# PX4FMUv2_4_6_1.net
KiCad netlist of a schematic drawn in Altium Designer
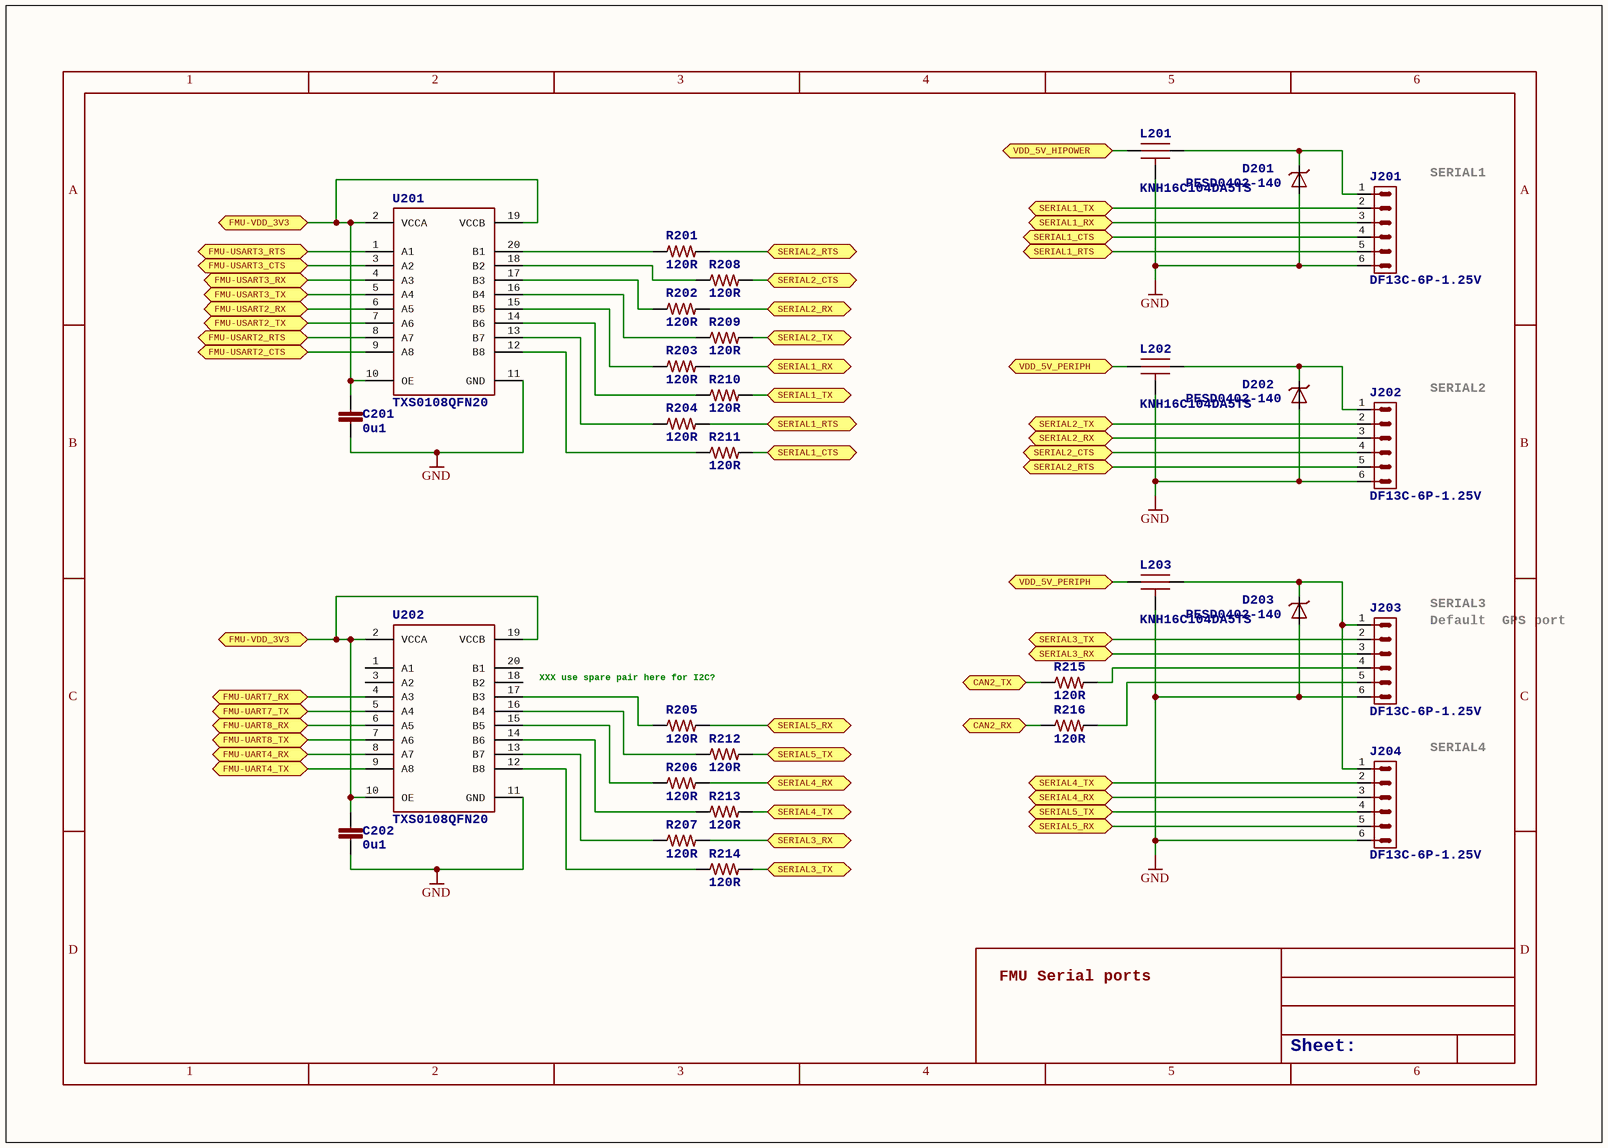
[diagram p0: PX4FMUv2.4.6_1.SchDoc]

(export (version "E")
  (design (tool "Eeschema 10.0.6"))
  (components
    (comp (ref "C201")
      (value "0u1")
      (footprint "0402-CAP")
      (description "CapacitorStandard 0603 ceramic capacitor, and 0.1\" leaded capacitor.")
      (fields (field (name "PARTNO") "CC0402ZRY5V7BB104"))
      (libsource (lib "pixhawk2") (part "CAP0402"))
    )
    (comp (ref "C202")
      (value "0u1")
      (footprint "0402-CAP")
      (description "CapacitorStandard 0603 ceramic capacitor, and 0.1\" leaded capacitor.")
      (fields (field (name "PARTNO") "CC0402ZRY5V7BB104"))
      (libsource (lib "pixhawk2") (part "CAP0402"))
    )
    (comp (ref "D201")
      (value "PESD0402-140")
      (footprint "0402-TVS")
      (libsource (lib "pixhawk2") (part "DIODE-TVS"))
    )
    (comp (ref "D202")
      (value "PESD0402-140")
      (footprint "0402-TVS")
      (libsource (lib "pixhawk2") (part "DIODE-TVS"))
    )
    (comp (ref "D203")
      (value "PESD0402-140")
      (footprint "0402-TVS")
      (libsource (lib "pixhawk2") (part "DIODE-TVS"))
    )
    (comp (ref "J201")
      (value "DF13C-6P-1.25V")
      (footprint "DF13C-6P-1.25V")
      (description "DF13-6P 1.25mm Pitch Miniature Crimping Connector.")
      (fields (field (name "PARTNO") "DF13C-6P-1.25V(20)"))
      (libsource (lib "con-hirose-df13") (part "DF13-6P-1.25V"))
    )
    (comp (ref "J202")
      (value "DF13C-6P-1.25V")
      (footprint "DF13C-6P-1.25V")
      (description "DF13-6P 1.25mm Pitch Miniature Crimping Connector.")
      (fields (field (name "PARTNO") "DF13C-6P-1.25V(20)"))
      (libsource (lib "con-hirose-df13") (part "DF13-6P-1.25V"))
    )
    (comp (ref "J203")
      (value "DF13C-6P-1.25V")
      (footprint "DF13C-6P-1.25V")
      (description "DF13-6P 1.25mm Pitch Miniature Crimping Connector.")
      (fields (field (name "PARTNO") "DF13C-6P-1.25V(20)"))
      (libsource (lib "con-hirose-df13") (part "DF13-6P-1.25V"))
    )
    (comp (ref "J204")
      (value "DF13C-6P-1.25V")
      (footprint "DF13C-6P-1.25V")
      (description "DF13-6P 1.25mm Pitch Miniature Crimping Connector.")
      (fields (field (name "PARTNO") "DF13C-6P-1.25V(20)"))
      (libsource (lib "con-hirose-df13") (part "DF13-6P-1.25V"))
    )
    (comp (ref "L201")
      (value "KNH16C104DA5TS")
      (footprint "KYOCERA-KNH16-DA")
      (description "Kyocera KNH16C104DA5TS EMI filter")
      (libsource (lib "pixhawk2") (part "KNH16C104DA5TS"))
    )
    (comp (ref "L202")
      (value "KNH16C104DA5TS")
      (footprint "KYOCERA-KNH16-DA")
      (description "Kyocera KNH16C104DA5TS EMI filter")
      (libsource (lib "pixhawk2") (part "KNH16C104DA5TS"))
    )
    (comp (ref "L203")
      (value "KNH16C104DA5TS")
      (footprint "KYOCERA-KNH16-DA")
      (description "Kyocera KNH16C104DA5TS EMI filter")
      (libsource (lib "pixhawk2") (part "KNH16C104DA5TS"))
    )
    (comp (ref "R201")
      (value "120R")
      (footprint "0402-RES")
      (fields (field (name "PARTNO") "RC0402FR-07120RL"))
      (libsource (lib "pixhawk2") (part "RESISTOR0402-RES"))
    )
    (comp (ref "R202")
      (value "120R")
      (footprint "0402-RES")
      (fields (field (name "PARTNO") "RC0402FR-07120RL"))
      (libsource (lib "pixhawk2") (part "RESISTOR0402-RES"))
    )
    (comp (ref "R203")
      (value "120R")
      (footprint "0402-RES")
      (fields (field (name "PARTNO") "RC0402FR-07120RL"))
      (libsource (lib "pixhawk2") (part "RESISTOR0402-RES"))
    )
    (comp (ref "R204")
      (value "120R")
      (footprint "0402-RES")
      (fields (field (name "PARTNO") "RC0402FR-07120RL"))
      (libsource (lib "pixhawk2") (part "RESISTOR0402-RES"))
    )
    (comp (ref "R205")
      (value "120R")
      (footprint "0402-RES")
      (fields (field (name "PARTNO") "RC0402FR-07120RL"))
      (libsource (lib "pixhawk2") (part "RESISTOR0402-RES"))
    )
    (comp (ref "R206")
      (value "120R")
      (footprint "0402-RES")
      (fields (field (name "PARTNO") "RC0402FR-07120RL"))
      (libsource (lib "pixhawk2") (part "RESISTOR0402-RES"))
    )
    (comp (ref "R207")
      (value "120R")
      (footprint "0402-RES")
      (fields (field (name "PARTNO") "RC0402FR-07120RL"))
      (libsource (lib "pixhawk2") (part "RESISTOR0402-RES"))
    )
    (comp (ref "R208")
      (value "120R")
      (footprint "0402-RES")
      (fields (field (name "PARTNO") "RC0402FR-07120RL"))
      (libsource (lib "pixhawk2") (part "RESISTOR0402-RES"))
    )
    (comp (ref "R209")
      (value "120R")
      (footprint "0402-RES")
      (fields (field (name "PARTNO") "RC0402FR-07120RL"))
      (libsource (lib "pixhawk2") (part "RESISTOR0402-RES"))
    )
    (comp (ref "R210")
      (value "120R")
      (footprint "0402-RES")
      (fields (field (name "PARTNO") "RC0402FR-07120RL"))
      (libsource (lib "pixhawk2") (part "RESISTOR0402-RES"))
    )
    (comp (ref "R211")
      (value "120R")
      (footprint "0402-RES")
      (fields (field (name "PARTNO") "RC0402FR-07120RL"))
      (libsource (lib "pixhawk2") (part "RESISTOR0402-RES"))
    )
    (comp (ref "R212")
      (value "120R")
      (footprint "0402-RES")
      (fields (field (name "PARTNO") "RC0402FR-07120RL"))
      (libsource (lib "pixhawk2") (part "RESISTOR0402-RES"))
    )
    (comp (ref "R213")
      (value "120R")
      (footprint "0402-RES")
      (fields (field (name "PARTNO") "RC0402FR-07120RL"))
      (libsource (lib "pixhawk2") (part "RESISTOR0402-RES"))
    )
    (comp (ref "R214")
      (value "120R")
      (footprint "0402-RES")
      (fields (field (name "PARTNO") "RC0402FR-07120RL"))
      (libsource (lib "pixhawk2") (part "RESISTOR0402-RES"))
    )
    (comp (ref "R215")
      (value "120R")
      (footprint "0402-RES")
      (fields (field (name "PARTNO") "RC0402FR-07120RL"))
      (libsource (lib "pixhawk2") (part "RESISTOR0402-RES"))
    )
    (comp (ref "R216")
      (value "120R")
      (footprint "0402-RES")
      (fields (field (name "PARTNO") "RC0402FR-07120RL"))
      (libsource (lib "pixhawk2") (part "RESISTOR0402-RES"))
    )
    (comp (ref "U201")
      (value "TXS0108QFN20")
      (footprint "QFN20-RGY")
      (fields (field (name "PARTNO") "TXS0108ERGYR"))
      (libsource (lib "pixhawk2") (part "TXS0108QFN20"))
    )
    (comp (ref "U202")
      (value "TXS0108QFN20")
      (footprint "QFN20-RGY")
      (fields (field (name "PARTNO") "TXS0108ERGYR"))
      (libsource (lib "pixhawk2") (part "TXS0108QFN20"))
    )
  )
  (nets
    (net (code "1") (name "/CAN2_RX") (class "Default")
      (node (ref "R216") (pin "P$1") (pinfunction "1_P$1") (pintype "passive"))
    )
    (net (code "2") (name "/CAN2_TX") (class "Default")
      (node (ref "R215") (pin "P$1") (pinfunction "1_P$1") (pintype "passive"))
    )
    (net (code "3") (name "/FMU-UART4_RX") (class "Default")
      (node (ref "U202") (pin "8") (pinfunction "A7_8") (pintype "passive"))
    )
    (net (code "4") (name "/FMU-UART4_TX") (class "Default")
      (node (ref "U202") (pin "9") (pinfunction "A8_9") (pintype "passive"))
    )
    (net (code "5") (name "/FMU-UART7_RX") (class "Default")
      (node (ref "U202") (pin "4") (pinfunction "A3_4") (pintype "passive"))
    )
    (net (code "6") (name "/FMU-UART7_TX") (class "Default")
      (node (ref "U202") (pin "5") (pinfunction "A4_5") (pintype "passive"))
    )
    (net (code "7") (name "/FMU-UART8_RX") (class "Default")
      (node (ref "U202") (pin "6") (pinfunction "A5_6") (pintype "passive"))
    )
    (net (code "8") (name "/FMU-UART8_TX") (class "Default")
      (node (ref "U202") (pin "7") (pinfunction "A6_7") (pintype "passive"))
    )
    (net (code "9") (name "/FMU-USART2_CTS") (class "Default")
      (node (ref "U201") (pin "9") (pinfunction "A8_9") (pintype "passive"))
    )
    (net (code "10") (name "/FMU-USART2_RTS") (class "Default")
      (node (ref "U201") (pin "8") (pinfunction "A7_8") (pintype "passive"))
    )
    (net (code "11") (name "/FMU-USART2_RX") (class "Default")
      (node (ref "U201") (pin "6") (pinfunction "A5_6") (pintype "passive"))
    )
    (net (code "12") (name "/FMU-USART2_TX") (class "Default")
      (node (ref "U201") (pin "7") (pinfunction "A6_7") (pintype "passive"))
    )
    (net (code "13") (name "/FMU-USART3_CTS") (class "Default")
      (node (ref "U201") (pin "3") (pinfunction "A2_3") (pintype "passive"))
    )
    (net (code "14") (name "/FMU-USART3_RTS") (class "Default")
      (node (ref "U201") (pin "1") (pinfunction "A1_1") (pintype "passive"))
    )
    (net (code "15") (name "/FMU-USART3_RX") (class "Default")
      (node (ref "U201") (pin "4") (pinfunction "A3_4") (pintype "passive"))
    )
    (net (code "16") (name "/FMU-USART3_TX") (class "Default")
      (node (ref "U201") (pin "5") (pinfunction "A4_5") (pintype "passive"))
    )
    (net (code "17") (name "/FMU-VDD_3V3") (class "Default")
      (node (ref "C201") (pin "P$1") (pinfunction "1_P$1") (pintype "passive"))
      (node (ref "C202") (pin "P$1") (pinfunction "1_P$1") (pintype "passive"))
      (node (ref "U201") (pin "10") (pinfunction "OE_10") (pintype "passive"))
      (node (ref "U201") (pin "19") (pinfunction "VCCB_19") (pintype "passive"))
      (node (ref "U201") (pin "2") (pinfunction "VCCA_2") (pintype "passive"))
      (node (ref "U202") (pin "10") (pinfunction "OE_10") (pintype "passive"))
      (node (ref "U202") (pin "19") (pinfunction "VCCB_19") (pintype "passive"))
      (node (ref "U202") (pin "2") (pinfunction "VCCA_2") (pintype "passive"))
    )
    (net (code "18") (name "/SERIAL1_CTS") (class "Default")
      (node (ref "J201") (pin "4") (pinfunction "4_4") (pintype "passive"))
      (node (ref "R211") (pin "P$2") (pinfunction "2_P$2") (pintype "passive"))
    )
    (net (code "19") (name "/SERIAL1_RTS") (class "Default")
      (node (ref "J201") (pin "5") (pinfunction "5_5") (pintype "passive"))
      (node (ref "R204") (pin "P$2") (pinfunction "2_P$2") (pintype "passive"))
    )
    (net (code "20") (name "/SERIAL1_RX") (class "Default")
      (node (ref "J201") (pin "3") (pinfunction "3_3") (pintype "passive"))
      (node (ref "R203") (pin "P$2") (pinfunction "2_P$2") (pintype "passive"))
    )
    (net (code "21") (name "/SERIAL1_TX") (class "Default")
      (node (ref "J201") (pin "2") (pinfunction "2_2") (pintype "passive"))
      (node (ref "R210") (pin "P$2") (pinfunction "2_P$2") (pintype "passive"))
    )
    (net (code "22") (name "/SERIAL2_CTS") (class "Default")
      (node (ref "J202") (pin "4") (pinfunction "4_4") (pintype "passive"))
      (node (ref "R208") (pin "P$2") (pinfunction "2_P$2") (pintype "passive"))
    )
    (net (code "23") (name "/SERIAL2_RTS") (class "Default")
      (node (ref "J202") (pin "5") (pinfunction "5_5") (pintype "passive"))
      (node (ref "R201") (pin "P$2") (pinfunction "2_P$2") (pintype "passive"))
    )
    (net (code "24") (name "/SERIAL2_RX") (class "Default")
      (node (ref "J202") (pin "3") (pinfunction "3_3") (pintype "passive"))
      (node (ref "R202") (pin "P$2") (pinfunction "2_P$2") (pintype "passive"))
    )
    (net (code "25") (name "/SERIAL2_TX") (class "Default")
      (node (ref "J202") (pin "2") (pinfunction "2_2") (pintype "passive"))
      (node (ref "R209") (pin "P$2") (pinfunction "2_P$2") (pintype "passive"))
    )
    (net (code "26") (name "/SERIAL3_RX") (class "Default")
      (node (ref "J203") (pin "3") (pinfunction "3_3") (pintype "passive"))
      (node (ref "R207") (pin "P$2") (pinfunction "2_P$2") (pintype "passive"))
    )
    (net (code "27") (name "/SERIAL3_TX") (class "Default")
      (node (ref "J203") (pin "2") (pinfunction "2_2") (pintype "passive"))
      (node (ref "R214") (pin "P$2") (pinfunction "2_P$2") (pintype "passive"))
    )
    (net (code "28") (name "/SERIAL4_RX") (class "Default")
      (node (ref "J204") (pin "3") (pinfunction "3_3") (pintype "passive"))
      (node (ref "R206") (pin "P$2") (pinfunction "2_P$2") (pintype "passive"))
    )
    (net (code "29") (name "/SERIAL4_TX") (class "Default")
      (node (ref "J204") (pin "2") (pinfunction "2_2") (pintype "passive"))
      (node (ref "R213") (pin "P$2") (pinfunction "2_P$2") (pintype "passive"))
    )
    (net (code "30") (name "/SERIAL5_RX") (class "Default")
      (node (ref "J204") (pin "5") (pinfunction "5_5") (pintype "passive"))
      (node (ref "R205") (pin "P$2") (pinfunction "2_P$2") (pintype "passive"))
    )
    (net (code "31") (name "/SERIAL5_TX") (class "Default")
      (node (ref "J204") (pin "4") (pinfunction "4_4") (pintype "passive"))
      (node (ref "R212") (pin "P$2") (pinfunction "2_P$2") (pintype "passive"))
    )
    (net (code "32") (name "/VDD_5V_HIPOWER") (class "Default")
      (node (ref "L201") (pin "P$1") (pinfunction "P$1_P$1") (pintype "passive"))
    )
    (net (code "33") (name "/VDD_5V_PERIPH") (class "Default")
      (node (ref "L202") (pin "P$1") (pinfunction "P$1_P$1") (pintype "passive"))
      (node (ref "L203") (pin "P$1") (pinfunction "P$1_P$1") (pintype "passive"))
    )
    (net (code "34") (name "GND") (class "Default")
      (node (ref "C201") (pin "P$2") (pinfunction "2_P$2") (pintype "passive"))
      (node (ref "C202") (pin "P$2") (pinfunction "2_P$2") (pintype "passive"))
      (node (ref "D201") (pin "A") (pinfunction "A_A") (pintype "passive"))
      (node (ref "D202") (pin "A") (pinfunction "A_A") (pintype "passive"))
      (node (ref "D203") (pin "A") (pinfunction "A_A") (pintype "passive"))
      (node (ref "J201") (pin "6") (pinfunction "6_6") (pintype "passive"))
      (node (ref "J202") (pin "6") (pinfunction "6_6") (pintype "passive"))
      (node (ref "J203") (pin "6") (pinfunction "6_6") (pintype "passive"))
      (node (ref "J204") (pin "6") (pinfunction "6_6") (pintype "passive"))
      (node (ref "L201") (pin "P$3_P$4_P$5") (pinfunction "P$3_P$3_P$4_P$5") (pintype "passive"))
      (node (ref "L202") (pin "P$3_P$4_P$5") (pinfunction "P$3_P$3_P$4_P$5") (pintype "passive"))
      (node (ref "L203") (pin "P$3_P$4_P$5") (pinfunction "P$3_P$3_P$4_P$5") (pintype "passive"))
      (node (ref "U201") (pin "11") (pinfunction "GND_11") (pintype "open_emitter"))
      (node (ref "U202") (pin "11") (pinfunction "GND_11") (pintype "open_emitter"))
    )
    (net (code "35") (name "Net-(D201-PadC)") (class "Default")
      (node (ref "D201") (pin "C") (pinfunction "C_C") (pintype "passive"))
      (node (ref "J201") (pin "1") (pinfunction "1_1") (pintype "passive"))
      (node (ref "L201") (pin "P$2") (pinfunction "P$2_P$2") (pintype "passive"))
    )
    (net (code "36") (name "Net-(D202-PadC)") (class "Default")
      (node (ref "D202") (pin "C") (pinfunction "C_C") (pintype "passive"))
      (node (ref "J202") (pin "1") (pinfunction "1_1") (pintype "passive"))
      (node (ref "L202") (pin "P$2") (pinfunction "P$2_P$2") (pintype "passive"))
    )
    (net (code "37") (name "Net-(D203-PadC)") (class "Default")
      (node (ref "D203") (pin "C") (pinfunction "C_C") (pintype "passive"))
      (node (ref "J203") (pin "1") (pinfunction "1_1") (pintype "passive"))
      (node (ref "J204") (pin "1") (pinfunction "1_1") (pintype "passive"))
      (node (ref "L203") (pin "P$2") (pinfunction "P$2_P$2") (pintype "passive"))
    )
    (net (code "38") (name "Net-(R201-1)") (class "Default")
      (node (ref "R201") (pin "P$1") (pinfunction "1_P$1") (pintype "passive"))
      (node (ref "U201") (pin "20") (pinfunction "B1_20") (pintype "passive"))
    )
    (net (code "39") (name "Net-(R202-1)") (class "Default")
      (node (ref "R202") (pin "P$1") (pinfunction "1_P$1") (pintype "passive"))
      (node (ref "U201") (pin "17") (pinfunction "B3_17") (pintype "passive"))
    )
    (net (code "40") (name "Net-(R203-1)") (class "Default")
      (node (ref "R203") (pin "P$1") (pinfunction "1_P$1") (pintype "passive"))
      (node (ref "U201") (pin "15") (pinfunction "B5_15") (pintype "passive"))
    )
    (net (code "41") (name "Net-(R204-1)") (class "Default")
      (node (ref "R204") (pin "P$1") (pinfunction "1_P$1") (pintype "passive"))
      (node (ref "U201") (pin "13") (pinfunction "B7_13") (pintype "passive"))
    )
    (net (code "42") (name "Net-(R205-1)") (class "Default")
      (node (ref "R205") (pin "P$1") (pinfunction "1_P$1") (pintype "passive"))
      (node (ref "U202") (pin "17") (pinfunction "B3_17") (pintype "passive"))
    )
    (net (code "43") (name "Net-(R206-1)") (class "Default")
      (node (ref "R206") (pin "P$1") (pinfunction "1_P$1") (pintype "passive"))
      (node (ref "U202") (pin "15") (pinfunction "B5_15") (pintype "passive"))
    )
    (net (code "44") (name "Net-(R207-1)") (class "Default")
      (node (ref "R207") (pin "P$1") (pinfunction "1_P$1") (pintype "passive"))
      (node (ref "U202") (pin "13") (pinfunction "B7_13") (pintype "passive"))
    )
    (net (code "45") (name "Net-(R208-1)") (class "Default")
      (node (ref "R208") (pin "P$1") (pinfunction "1_P$1") (pintype "passive"))
      (node (ref "U201") (pin "18") (pinfunction "B2_18") (pintype "passive"))
    )
    (net (code "46") (name "Net-(R209-1)") (class "Default")
      (node (ref "R209") (pin "P$1") (pinfunction "1_P$1") (pintype "passive"))
      (node (ref "U201") (pin "16") (pinfunction "B4_16") (pintype "passive"))
    )
    (net (code "47") (name "Net-(R210-1)") (class "Default")
      (node (ref "R210") (pin "P$1") (pinfunction "1_P$1") (pintype "passive"))
      (node (ref "U201") (pin "14") (pinfunction "B6_14") (pintype "passive"))
    )
    (net (code "48") (name "Net-(R211-1)") (class "Default")
      (node (ref "R211") (pin "P$1") (pinfunction "1_P$1") (pintype "passive"))
      (node (ref "U201") (pin "12") (pinfunction "B8_12") (pintype "passive"))
    )
    (net (code "49") (name "Net-(R212-1)") (class "Default")
      (node (ref "R212") (pin "P$1") (pinfunction "1_P$1") (pintype "passive"))
      (node (ref "U202") (pin "16") (pinfunction "B4_16") (pintype "passive"))
    )
    (net (code "50") (name "Net-(R213-1)") (class "Default")
      (node (ref "R213") (pin "P$1") (pinfunction "1_P$1") (pintype "passive"))
      (node (ref "U202") (pin "14") (pinfunction "B6_14") (pintype "passive"))
    )
    (net (code "51") (name "Net-(R214-1)") (class "Default")
      (node (ref "R214") (pin "P$1") (pinfunction "1_P$1") (pintype "passive"))
      (node (ref "U202") (pin "12") (pinfunction "B8_12") (pintype "passive"))
    )
    (net (code "52") (name "Net-(R215-2)") (class "Default")
      (node (ref "J203") (pin "4") (pinfunction "4_4") (pintype "passive"))
      (node (ref "R215") (pin "P$2") (pinfunction "2_P$2") (pintype "passive"))
    )
    (net (code "53") (name "Net-(R216-2)") (class "Default")
      (node (ref "J203") (pin "5") (pinfunction "5_5") (pintype "passive"))
      (node (ref "R216") (pin "P$2") (pinfunction "2_P$2") (pintype "passive"))
    )
    (net (code "54") (name "unconnected-(U202-A1-Pad1)") (class "Default")
      (node (ref "U202") (pin "1") (pinfunction "A1_1") (pintype "passive"))
    )
    (net (code "55") (name "unconnected-(U202-A2-Pad3)") (class "Default")
      (node (ref "U202") (pin "3") (pinfunction "A2_3") (pintype "passive"))
    )
    (net (code "56") (name "unconnected-(U202-B1-Pad20)") (class "Default")
      (node (ref "U202") (pin "20") (pinfunction "B1_20") (pintype "passive"))
    )
    (net (code "57") (name "unconnected-(U202-B2-Pad18)") (class "Default")
      (node (ref "U202") (pin "18") (pinfunction "B2_18") (pintype "passive"))
    )
  )
)
